# Signal_conditioning.net
KiCad netlist of a schematic drawn in Altium Designer
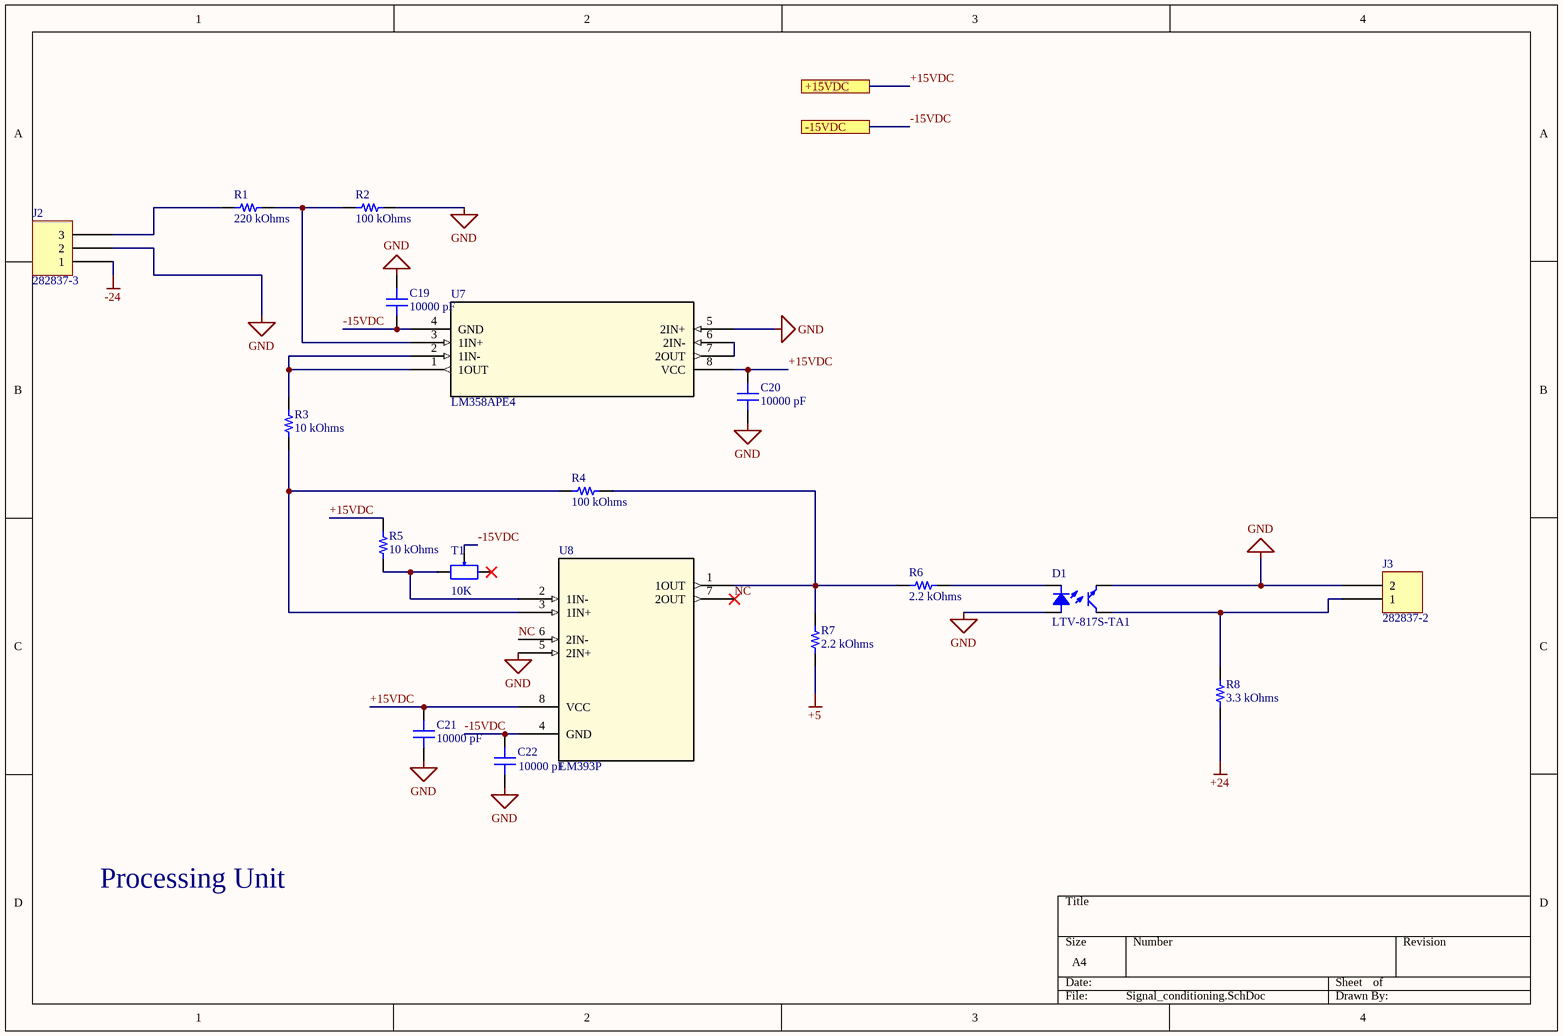
[diagram p0: Signal_conditioning.SchDoc]

(export (version "E")
  (design (tool "Eeschema 10.0.6"))
  (components
    (comp (ref "C19")
      (value "10000 pF")
      (footprint "CAP 0805_2012")
      (description "CAP CER 0805 10NF 25V C0G 1%")
      (fields
        (field (name "PART NUMBER") "C0805C103F3GEC7800")
        (field (name "CAPACITANCE") "10000 pF")
        (field (name "MANUFACTURER") "KEMET")
      )
      (libsource (lib "Celestial Altium Library - altium_library") (part "Capacitor"))
    )
    (comp (ref "C20")
      (value "10000 pF")
      (footprint "CAP 0805_2012")
      (description "CAP CER 0805 10NF 25V C0G 1%")
      (fields
        (field (name "PART NUMBER") "C0805C103F3GEC7800")
        (field (name "CAPACITANCE") "10000 pF")
        (field (name "MANUFACTURER") "KEMET")
      )
      (libsource (lib "Celestial Altium Library - altium_library") (part "Capacitor"))
    )
    (comp (ref "C21")
      (value "10000 pF")
      (footprint "CAP 0805_2012")
      (description "CAP CER 0805 10NF 25V C0G 1%")
      (fields
        (field (name "PART NUMBER") "C0805C103F3GEC7800")
        (field (name "CAPACITANCE") "10000 pF")
        (field (name "MANUFACTURER") "KEMET")
      )
      (libsource (lib "Celestial Altium Library - altium_library") (part "Capacitor"))
    )
    (comp (ref "C22")
      (value "10000 pF")
      (footprint "CAP 0805_2012")
      (description "CAP CER 0805 10NF 25V C0G 1%")
      (fields
        (field (name "PART NUMBER") "C0805C103F3GEC7800")
        (field (name "CAPACITANCE") "10000 pF")
        (field (name "MANUFACTURER") "KEMET")
      )
      (libsource (lib "Celestial Altium Library - altium_library") (part "Capacitor"))
    )
    (comp (ref "D1")
      (value "LTV-817S-TA1")
      (footprint "LITEON LTV-817")
      (description "OPTOISOLATR 5KV TRANSISTOR 4-SMD")
      (fields (field (name "MANUFACTURER") "Lite-On Inc."))
      (libsource (lib "Celestial Altium Library - altium_library") (part "Optoisolator"))
    )
    (comp (ref "J2")
      (value "282837-3")
      (footprint "TE 282837-3")
      (description "TERM BLK 3P SIDE ENT 5.08MM PCB")
      (fields (field (name "MANUFACTURER") "TE Connectivity AMP Connectors") (field (name "VOLTAGE") "300 V"))
      (libsource (lib "Celestial Altium Library - altium_library") (part "3 Pin"))
    )
    (comp (ref "J3")
      (value "282837-2")
      (footprint "TE 282837-2")
      (description "TERM BLK 2P SIDE ENT 5.08MM PCB")
      (fields (field (name "MANUFACTURER") "TE Connectivity AMP Connectors") (field (name "VOLTAGE") "300 V"))
      (libsource (lib "Celestial Altium Library - altium_library") (part "2 Pin"))
    )
    (comp (ref "R1")
      (value "220 kOhms")
      (footprint "RES 1206_3216")
      (description "RES SMD 220K OHM 0.1% 1/4W 1206")
      (fields (field (name "PART NUMBER") "RT1206BRD07220KL") (field (name "MANUFACTURER") "Yageo"))
      (libsource (lib "Celestial Altium Library - altium_library") (part "Resistor"))
    )
    (comp (ref "R2")
      (value "100 kOhms")
      (footprint "RES 1206_3216")
      (description "RES 100K OHM 0.1% 1/8W 1206")
      (fields
        (field (name "PART NUMBER") "RNCS1206BKE100K")
        (field (name "MANUFACTURER") "Stackpole Electronics Inc")
      )
      (libsource (lib "Celestial Altium Library - altium_library") (part "Resistor"))
    )
    (comp (ref "R3")
      (value "10 kOhms")
      (footprint "RES 1206_3216")
      (description "RES SMD 10K OHM 1% 1/4W 1206")
      (fields
        (field (name "PART NUMBER") "CRG1206F10K")
        (field (name "MANUFACTURER") "TE Connectivity Passive Product")
      )
      (libsource (lib "Celestial Altium Library - altium_library") (part "Resistor"))
    )
    (comp (ref "R4")
      (value "100 kOhms")
      (footprint "RES 1206_3216")
      (description "RES 100K OHM 0.1% 1/8W 1206")
      (fields
        (field (name "PART NUMBER") "RNCS1206BKE100K")
        (field (name "MANUFACTURER") "Stackpole Electronics Inc")
      )
      (libsource (lib "Celestial Altium Library - altium_library") (part "Resistor"))
    )
    (comp (ref "R5")
      (value "10 kOhms")
      (footprint "RES 1206_3216")
      (description "RES SMD 10K OHM 1% 1/4W 1206")
      (fields
        (field (name "PART NUMBER") "CRG1206F10K")
        (field (name "MANUFACTURER") "TE Connectivity Passive Product")
      )
      (libsource (lib "Celestial Altium Library - altium_library") (part "Resistor"))
    )
    (comp (ref "R6")
      (value "2.2 kOhms")
      (footprint "RES 1206_3216")
      (description "RES SMD 2.2K OHM 0.1% 1/4W 1206")
      (fields (field (name "PART NUMBER") "RT1206BRD072K2L") (field (name "MANUFACTURER") "Yageo"))
      (libsource (lib "Celestial Altium Library - altium_library") (part "Resistor"))
    )
    (comp (ref "R7")
      (value "2.2 kOhms")
      (footprint "RES 1206_3216")
      (description "RES SMD 2.2K OHM 0.1% 1/4W 1206")
      (fields (field (name "PART NUMBER") "RT1206BRD072K2L") (field (name "MANUFACTURER") "Yageo"))
      (libsource (lib "Celestial Altium Library - altium_library") (part "Resistor"))
    )
    (comp (ref "R8")
      (value "3.3 kOhms")
      (footprint "RES 1206_3216")
      (description "RES SMD 3.3K OHM 5% 1/4W 1206")
      (fields (field (name "PART NUMBER") "AC1206JR-073K3L") (field (name "MANUFACTURER") "Yageo"))
      (libsource (lib "Celestial Altium Library - altium_library") (part "Resistor"))
    )
    (comp (ref "T1")
      (value "10K")
      (footprint "Bien Tro Vi Chinh Dung")
      (description "Cắm")
      (libsource (lib "Resistor") (part "Bien Tro Tinh Chinh 10K Dung"))
    )
    (comp (ref "U7")
      (value "LM358APE4")
      (footprint "P8")
      (description "Dual, 30-V, 700-kHz operational amplifier 8-PDIP 0 to 70")
      (fields (field (name "COPYRIGHT") "Copyright (C) 2025 Ultra Librarian. All rights reserved."))
      (libsource (lib "LM358APE4") (part "LM358APE4"))
    )
    (comp (ref "U8")
      (value "LM393P")
      (footprint "P8")
      (description "Dual differential comparator, commercial grade 8-PDIP 0 to 70")
      (fields (field (name "COPYRIGHT") "Copyright (C) 2026 Ultra Librarian. All rights reserved."))
      (libsource (lib "LM393P") (part "LM393P"))
    )
  )
  (nets
    (net (code "1") (name "+5") (class "Default")
      (node (ref "R7") (pin "1") (pinfunction "1_1") (pintype "passive"))
    )
    (net (code "2") (name "+24") (class "Default")
      (node (ref "R8") (pin "1") (pinfunction "1_1") (pintype "passive"))
    )
    (net (code "3") (name "-24") (class "Default")
      (node (ref "J2") (pin "1") (pinfunction "1_1") (pintype "passive"))
    )
    (net (code "4") (name "/+15VDC") (class "Default")
      (node (ref "C20") (pin "1") (pinfunction "1_1") (pintype "passive"))
      (node (ref "C21") (pin "1") (pinfunction "1_1") (pintype "passive"))
      (node (ref "R5") (pin "1") (pinfunction "1_1") (pintype "passive"))
      (node (ref "U7") (pin "8") (pinfunction "VCC_8") (pintype "power_in"))
      (node (ref "U8") (pin "8") (pinfunction "VCC_8") (pintype "power_in"))
    )
    (net (code "5") (name "/-15VDC") (class "Default")
      (node (ref "C19") (pin "2") (pinfunction "2_2") (pintype "passive"))
      (node (ref "C22") (pin "1") (pinfunction "1_1") (pintype "passive"))
      (node (ref "T1") (pin "2") (pinfunction "2_2") (pintype "passive"))
      (node (ref "U7") (pin "4") (pinfunction "GND_4") (pintype "power_in"))
      (node (ref "U8") (pin "4") (pinfunction "GND_4") (pintype "power_in"))
    )
    (net (code "6") (name "/NC") (class "Default")
      (node (ref "U8") (pin "6") (pinfunction "2IN-_6") (pintype "input"))
      (node (ref "U8") (pin "7") (pinfunction "2OUT_7") (pintype "output"))
    )
    (net (code "7") (name "GND") (class "Default")
      (node (ref "C19") (pin "1") (pinfunction "1_1") (pintype "passive"))
      (node (ref "C20") (pin "2") (pinfunction "2_2") (pintype "passive"))
      (node (ref "C21") (pin "2") (pinfunction "2_2") (pintype "passive"))
      (node (ref "C22") (pin "2") (pinfunction "2_2") (pintype "passive"))
      (node (ref "D1") (pin "1") (pinfunction "1_1") (pintype "passive"))
      (node (ref "D1") (pin "3") (pinfunction "3_3") (pintype "passive"))
      (node (ref "J2") (pin "2") (pinfunction "2_2") (pintype "passive"))
      (node (ref "J3") (pin "2") (pinfunction "2_2") (pintype "passive"))
      (node (ref "R2") (pin "2") (pinfunction "2_2") (pintype "passive"))
      (node (ref "U7") (pin "5") (pinfunction "2IN+_5") (pintype "input"))
      (node (ref "U8") (pin "5") (pinfunction "2IN+_5") (pintype "input"))
    )
    (net (code "8") (name "Net-(D1-Pad2)") (class "Default")
      (node (ref "D1") (pin "2") (pinfunction "2_2") (pintype "passive"))
      (node (ref "R6") (pin "2") (pinfunction "2_2") (pintype "passive"))
    )
    (net (code "9") (name "Net-(D1-Pad4)") (class "Default")
      (node (ref "D1") (pin "4") (pinfunction "4_4") (pintype "passive"))
      (node (ref "J3") (pin "1") (pinfunction "1_1") (pintype "passive"))
      (node (ref "R8") (pin "2") (pinfunction "2_2") (pintype "passive"))
    )
    (net (code "10") (name "Net-(J2-Pad3)") (class "Default")
      (node (ref "J2") (pin "3") (pinfunction "3_3") (pintype "passive"))
      (node (ref "R1") (pin "1") (pinfunction "1_1") (pintype "passive"))
    )
    (net (code "11") (name "Net-(U7-1IN+)") (class "Default")
      (node (ref "R1") (pin "2") (pinfunction "2_2") (pintype "passive"))
      (node (ref "R2") (pin "1") (pinfunction "1_1") (pintype "passive"))
      (node (ref "U7") (pin "3") (pinfunction "1IN+_3") (pintype "input"))
    )
    (net (code "12") (name "Net-(U7-1IN-)") (class "Default")
      (node (ref "R3") (pin "2") (pinfunction "2_2") (pintype "passive"))
      (node (ref "U7") (pin "1") (pinfunction "1OUT_1") (pintype "output"))
      (node (ref "U7") (pin "2") (pinfunction "1IN-_2") (pintype "input"))
    )
    (net (code "13") (name "Net-(U7-2IN-)") (class "Default")
      (node (ref "U7") (pin "6") (pinfunction "2IN-_6") (pintype "input"))
      (node (ref "U7") (pin "7") (pinfunction "2OUT_7") (pintype "output"))
    )
    (net (code "14") (name "Net-(U8-1IN+)") (class "Default")
      (node (ref "R3") (pin "1") (pinfunction "1_1") (pintype "passive"))
      (node (ref "R4") (pin "1") (pinfunction "1_1") (pintype "passive"))
      (node (ref "U8") (pin "3") (pinfunction "1IN+_3") (pintype "input"))
    )
    (net (code "15") (name "Net-(U8-1IN-)") (class "Default")
      (node (ref "R5") (pin "2") (pinfunction "2_2") (pintype "passive"))
      (node (ref "T1") (pin "1") (pinfunction "1_1") (pintype "passive"))
      (node (ref "U8") (pin "2") (pinfunction "1IN-_2") (pintype "input"))
    )
    (net (code "16") (name "Net-(U8-1OUT)") (class "Default")
      (node (ref "R4") (pin "2") (pinfunction "2_2") (pintype "passive"))
      (node (ref "R6") (pin "1") (pinfunction "1_1") (pintype "passive"))
      (node (ref "R7") (pin "2") (pinfunction "2_2") (pintype "passive"))
      (node (ref "U8") (pin "1") (pinfunction "1OUT_1") (pintype "output"))
    )
    (net (code "17") (name "unconnected-(T1-Pad3)") (class "Default")
      (node (ref "T1") (pin "3") (pinfunction "3_3") (pintype "passive+no_connect"))
    )
  )
)
